# home_audio_logic_psu_v0001.net
KiCad netlist of a schematic drawn in EAGLE
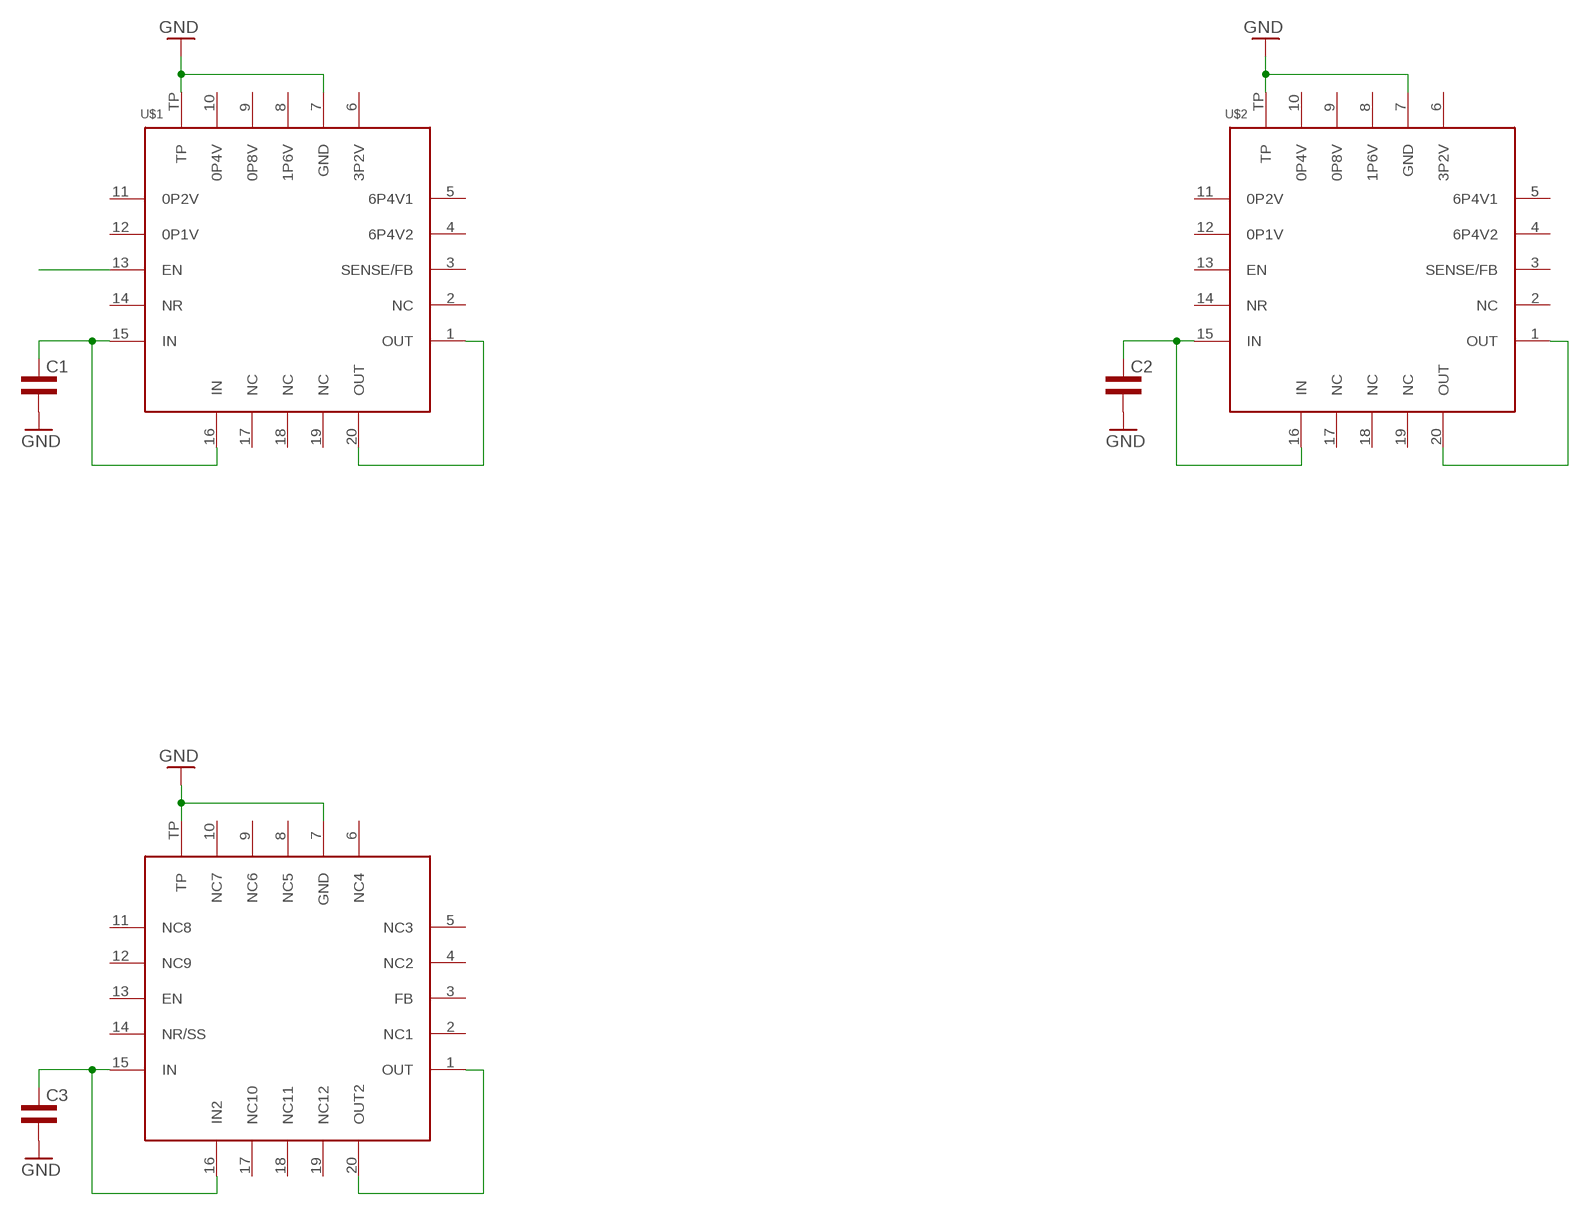
[diagram p0: schematic, sheet 1]

(export (version "E")
  (design (tool "Eeschema 10.0.6"))
  (components
    (comp (ref "C1")
      (value "CAP1206L3")
      (footprint "eagle-import:1206L3")
      (libsource (lib "eagle-import") (part "CAP1206L3"))
    )
    (comp (ref "C2")
      (value "CAP1206L3")
      (footprint "eagle-import:1206L3")
      (libsource (lib "eagle-import") (part "CAP1206L3"))
    )
    (comp (ref "C3")
      (value "CAP1206L3")
      (footprint "eagle-import:1206L3")
      (libsource (lib "eagle-import") (part "CAP1206L3"))
    )
    (comp (ref "U$1")
      (value "POWER-SUPPLY_POS_V1_TI_LDO_TPS7A4700")
      (footprint "eagle-import:POWER-SUPPLY_POS_V1_TI_LDO_VQFN-20")
      (libsource (lib "eagle-import") (part "POWER-SUPPLY_POS_V1_TI_LDO_TPS7A4700"))
    )
    (comp (ref "U$2")
      (value "POWER-SUPPLY_POS_V1_TI_LDO_TPS7A4700")
      (footprint "eagle-import:POWER-SUPPLY_POS_V1_TI_LDO_VQFN-20")
      (libsource (lib "eagle-import") (part "POWER-SUPPLY_POS_V1_TI_LDO_TPS7A4700"))
    )
    (comp (ref "U$3")
      (value "POWER-SUPPLY_POS_V1_TI_LDO_TPS7A3301RGWT")
      (footprint "eagle-import:POWER-SUPPLY_POS_V1_TI_LDO_VQFN-20")
      (libsource (lib "eagle-import") (part "POWER-SUPPLY_POS_V1_TI_LDO_TPS7A3301RGWT"))
    )
  )
  (nets
    (net (code "1") (name "GND") (class "Default")
      (node (ref "C1") (pin "2") (pinfunction "2_2") (pintype "bidirectional"))
      (node (ref "C2") (pin "2") (pinfunction "2_2") (pintype "bidirectional"))
      (node (ref "C3") (pin "2") (pinfunction "2_2") (pintype "bidirectional"))
      (node (ref "U$1") (pin "7") (pinfunction "GND_7") (pintype "bidirectional"))
      (node (ref "U$1") (pin "TP") (pinfunction "TP_TP") (pintype "bidirectional"))
      (node (ref "U$2") (pin "7") (pinfunction "GND_7") (pintype "bidirectional"))
      (node (ref "U$2") (pin "TP") (pinfunction "TP_TP") (pintype "bidirectional"))
      (node (ref "U$3") (pin "7") (pinfunction "GND_7") (pintype "bidirectional"))
      (node (ref "U$3") (pin "TP") (pinfunction "TP_TP") (pintype "bidirectional"))
    )
    (net (code "2") (name "Net-(C1-Pad1)") (class "Default")
      (node (ref "C1") (pin "1") (pinfunction "1_1") (pintype "bidirectional"))
      (node (ref "U$1") (pin "15") (pinfunction "IN_15") (pintype "bidirectional"))
      (node (ref "U$1") (pin "16") (pinfunction "IN_16") (pintype "bidirectional"))
    )
    (net (code "3") (name "Net-(C2-Pad1)") (class "Default")
      (node (ref "C2") (pin "1") (pinfunction "1_1") (pintype "bidirectional"))
      (node (ref "U$2") (pin "15") (pinfunction "IN_15") (pintype "bidirectional"))
      (node (ref "U$2") (pin "16") (pinfunction "IN_16") (pintype "bidirectional"))
    )
    (net (code "4") (name "Net-(U$1-OUT-Pad1)") (class "Default")
      (node (ref "U$1") (pin "1") (pinfunction "OUT_1") (pintype "bidirectional"))
      (node (ref "U$1") (pin "20") (pinfunction "OUT_20") (pintype "bidirectional"))
    )
    (net (code "5") (name "Net-(U$2-OUT-Pad1)") (class "Default")
      (node (ref "U$2") (pin "1") (pinfunction "OUT_1") (pintype "bidirectional"))
      (node (ref "U$2") (pin "20") (pinfunction "OUT_20") (pintype "bidirectional"))
    )
    (net (code "6") (name "Net-(U$3-IN)") (class "Default")
      (node (ref "C3") (pin "1") (pinfunction "1_1") (pintype "bidirectional"))
      (node (ref "U$3") (pin "15") (pinfunction "IN_15") (pintype "bidirectional"))
      (node (ref "U$3") (pin "16") (pinfunction "IN2_16") (pintype "bidirectional"))
    )
    (net (code "7") (name "Net-(U$3-OUT)") (class "Default")
      (node (ref "U$3") (pin "1") (pinfunction "OUT_1") (pintype "bidirectional"))
      (node (ref "U$3") (pin "20") (pinfunction "OUT2_20") (pintype "bidirectional"))
    )
    (net (code "8") (name "unconnected-(U$1-0P1V-Pad12)") (class "Default")
      (node (ref "U$1") (pin "12") (pinfunction "0P1V_12") (pintype "bidirectional"))
    )
    (net (code "9") (name "unconnected-(U$1-0P2V-Pad11)") (class "Default")
      (node (ref "U$1") (pin "11") (pinfunction "0P2V_11") (pintype "bidirectional"))
    )
    (net (code "10") (name "unconnected-(U$1-0P4V-Pad10)") (class "Default")
      (node (ref "U$1") (pin "10") (pinfunction "0P4V_10") (pintype "bidirectional"))
    )
    (net (code "11") (name "unconnected-(U$1-0P8V-Pad9)") (class "Default")
      (node (ref "U$1") (pin "9") (pinfunction "0P8V_9") (pintype "bidirectional"))
    )
    (net (code "12") (name "unconnected-(U$1-1P6V-Pad8)") (class "Default")
      (node (ref "U$1") (pin "8") (pinfunction "1P6V_8") (pintype "bidirectional"))
    )
    (net (code "13") (name "unconnected-(U$1-3P2V-Pad6)") (class "Default")
      (node (ref "U$1") (pin "6") (pinfunction "3P2V_6") (pintype "bidirectional"))
    )
    (net (code "14") (name "unconnected-(U$1-6P4V1-Pad5)") (class "Default")
      (node (ref "U$1") (pin "5") (pinfunction "6P4V1_5") (pintype "bidirectional"))
    )
    (net (code "15") (name "unconnected-(U$1-6P4V2-Pad4)") (class "Default")
      (node (ref "U$1") (pin "4") (pinfunction "6P4V2_4") (pintype "bidirectional"))
    )
    (net (code "16") (name "unconnected-(U$1-EN-Pad13)") (class "Default")
      (node (ref "U$1") (pin "13") (pinfunction "EN_13") (pintype "bidirectional"))
    )
    (net (code "17") (name "unconnected-(U$1-NC-Pad2)") (class "Default")
      (node (ref "U$1") (pin "2") (pinfunction "NC_2") (pintype "bidirectional"))
    )
    (net (code "18") (name "unconnected-(U$1-NC-Pad17)") (class "Default")
      (node (ref "U$1") (pin "17") (pinfunction "NC_17") (pintype "bidirectional"))
    )
    (net (code "19") (name "unconnected-(U$1-NC-Pad18)") (class "Default")
      (node (ref "U$1") (pin "18") (pinfunction "NC_18") (pintype "bidirectional"))
    )
    (net (code "20") (name "unconnected-(U$1-NC-Pad19)") (class "Default")
      (node (ref "U$1") (pin "19") (pinfunction "NC_19") (pintype "bidirectional"))
    )
    (net (code "21") (name "unconnected-(U$1-NR-Pad14)") (class "Default")
      (node (ref "U$1") (pin "14") (pinfunction "NR_14") (pintype "bidirectional"))
    )
    (net (code "22") (name "unconnected-(U$1-SENSE{slash}FB-Pad3)") (class "Default")
      (node (ref "U$1") (pin "3") (pinfunction "SENSE/FB_3") (pintype "bidirectional"))
    )
    (net (code "23") (name "unconnected-(U$2-0P1V-Pad12)") (class "Default")
      (node (ref "U$2") (pin "12") (pinfunction "0P1V_12") (pintype "bidirectional"))
    )
    (net (code "24") (name "unconnected-(U$2-0P2V-Pad11)") (class "Default")
      (node (ref "U$2") (pin "11") (pinfunction "0P2V_11") (pintype "bidirectional"))
    )
    (net (code "25") (name "unconnected-(U$2-0P4V-Pad10)") (class "Default")
      (node (ref "U$2") (pin "10") (pinfunction "0P4V_10") (pintype "bidirectional"))
    )
    (net (code "26") (name "unconnected-(U$2-0P8V-Pad9)") (class "Default")
      (node (ref "U$2") (pin "9") (pinfunction "0P8V_9") (pintype "bidirectional"))
    )
    (net (code "27") (name "unconnected-(U$2-1P6V-Pad8)") (class "Default")
      (node (ref "U$2") (pin "8") (pinfunction "1P6V_8") (pintype "bidirectional"))
    )
    (net (code "28") (name "unconnected-(U$2-3P2V-Pad6)") (class "Default")
      (node (ref "U$2") (pin "6") (pinfunction "3P2V_6") (pintype "bidirectional"))
    )
    (net (code "29") (name "unconnected-(U$2-6P4V1-Pad5)") (class "Default")
      (node (ref "U$2") (pin "5") (pinfunction "6P4V1_5") (pintype "bidirectional"))
    )
    (net (code "30") (name "unconnected-(U$2-6P4V2-Pad4)") (class "Default")
      (node (ref "U$2") (pin "4") (pinfunction "6P4V2_4") (pintype "bidirectional"))
    )
    (net (code "31") (name "unconnected-(U$2-EN-Pad13)") (class "Default")
      (node (ref "U$2") (pin "13") (pinfunction "EN_13") (pintype "bidirectional"))
    )
    (net (code "32") (name "unconnected-(U$2-NC-Pad2)") (class "Default")
      (node (ref "U$2") (pin "2") (pinfunction "NC_2") (pintype "bidirectional"))
    )
    (net (code "33") (name "unconnected-(U$2-NC-Pad17)") (class "Default")
      (node (ref "U$2") (pin "17") (pinfunction "NC_17") (pintype "bidirectional"))
    )
    (net (code "34") (name "unconnected-(U$2-NC-Pad18)") (class "Default")
      (node (ref "U$2") (pin "18") (pinfunction "NC_18") (pintype "bidirectional"))
    )
    (net (code "35") (name "unconnected-(U$2-NC-Pad19)") (class "Default")
      (node (ref "U$2") (pin "19") (pinfunction "NC_19") (pintype "bidirectional"))
    )
    (net (code "36") (name "unconnected-(U$2-NR-Pad14)") (class "Default")
      (node (ref "U$2") (pin "14") (pinfunction "NR_14") (pintype "bidirectional"))
    )
    (net (code "37") (name "unconnected-(U$2-SENSE{slash}FB-Pad3)") (class "Default")
      (node (ref "U$2") (pin "3") (pinfunction "SENSE/FB_3") (pintype "bidirectional"))
    )
    (net (code "38") (name "unconnected-(U$3-EN-Pad13)") (class "Default")
      (node (ref "U$3") (pin "13") (pinfunction "EN_13") (pintype "bidirectional"))
    )
    (net (code "39") (name "unconnected-(U$3-FB-Pad3)") (class "Default")
      (node (ref "U$3") (pin "3") (pinfunction "FB_3") (pintype "bidirectional"))
    )
    (net (code "40") (name "unconnected-(U$3-NC1-Pad2)") (class "Default")
      (node (ref "U$3") (pin "2") (pinfunction "NC1_2") (pintype "bidirectional"))
    )
    (net (code "41") (name "unconnected-(U$3-NC2-Pad4)") (class "Default")
      (node (ref "U$3") (pin "4") (pinfunction "NC2_4") (pintype "bidirectional"))
    )
    (net (code "42") (name "unconnected-(U$3-NC3-Pad5)") (class "Default")
      (node (ref "U$3") (pin "5") (pinfunction "NC3_5") (pintype "bidirectional"))
    )
    (net (code "43") (name "unconnected-(U$3-NC4-Pad6)") (class "Default")
      (node (ref "U$3") (pin "6") (pinfunction "NC4_6") (pintype "bidirectional"))
    )
    (net (code "44") (name "unconnected-(U$3-NC5-Pad8)") (class "Default")
      (node (ref "U$3") (pin "8") (pinfunction "NC5_8") (pintype "bidirectional"))
    )
    (net (code "45") (name "unconnected-(U$3-NC6-Pad9)") (class "Default")
      (node (ref "U$3") (pin "9") (pinfunction "NC6_9") (pintype "bidirectional"))
    )
    (net (code "46") (name "unconnected-(U$3-NC7-Pad10)") (class "Default")
      (node (ref "U$3") (pin "10") (pinfunction "NC7_10") (pintype "bidirectional"))
    )
    (net (code "47") (name "unconnected-(U$3-NC8-Pad11)") (class "Default")
      (node (ref "U$3") (pin "11") (pinfunction "NC8_11") (pintype "bidirectional"))
    )
    (net (code "48") (name "unconnected-(U$3-NC9-Pad12)") (class "Default")
      (node (ref "U$3") (pin "12") (pinfunction "NC9_12") (pintype "bidirectional"))
    )
    (net (code "49") (name "unconnected-(U$3-NC10-Pad17)") (class "Default")
      (node (ref "U$3") (pin "17") (pinfunction "NC10_17") (pintype "bidirectional"))
    )
    (net (code "50") (name "unconnected-(U$3-NC11-Pad18)") (class "Default")
      (node (ref "U$3") (pin "18") (pinfunction "NC11_18") (pintype "bidirectional"))
    )
    (net (code "51") (name "unconnected-(U$3-NC12-Pad19)") (class "Default")
      (node (ref "U$3") (pin "19") (pinfunction "NC12_19") (pintype "bidirectional"))
    )
    (net (code "52") (name "unconnected-(U$3-NR{slash}SS-Pad14)") (class "Default")
      (node (ref "U$3") (pin "14") (pinfunction "NR/SS_14") (pintype "bidirectional"))
    )
  )
)
